# LCD-24.net
KiCad netlist of a schematic drawn in Altium Designer
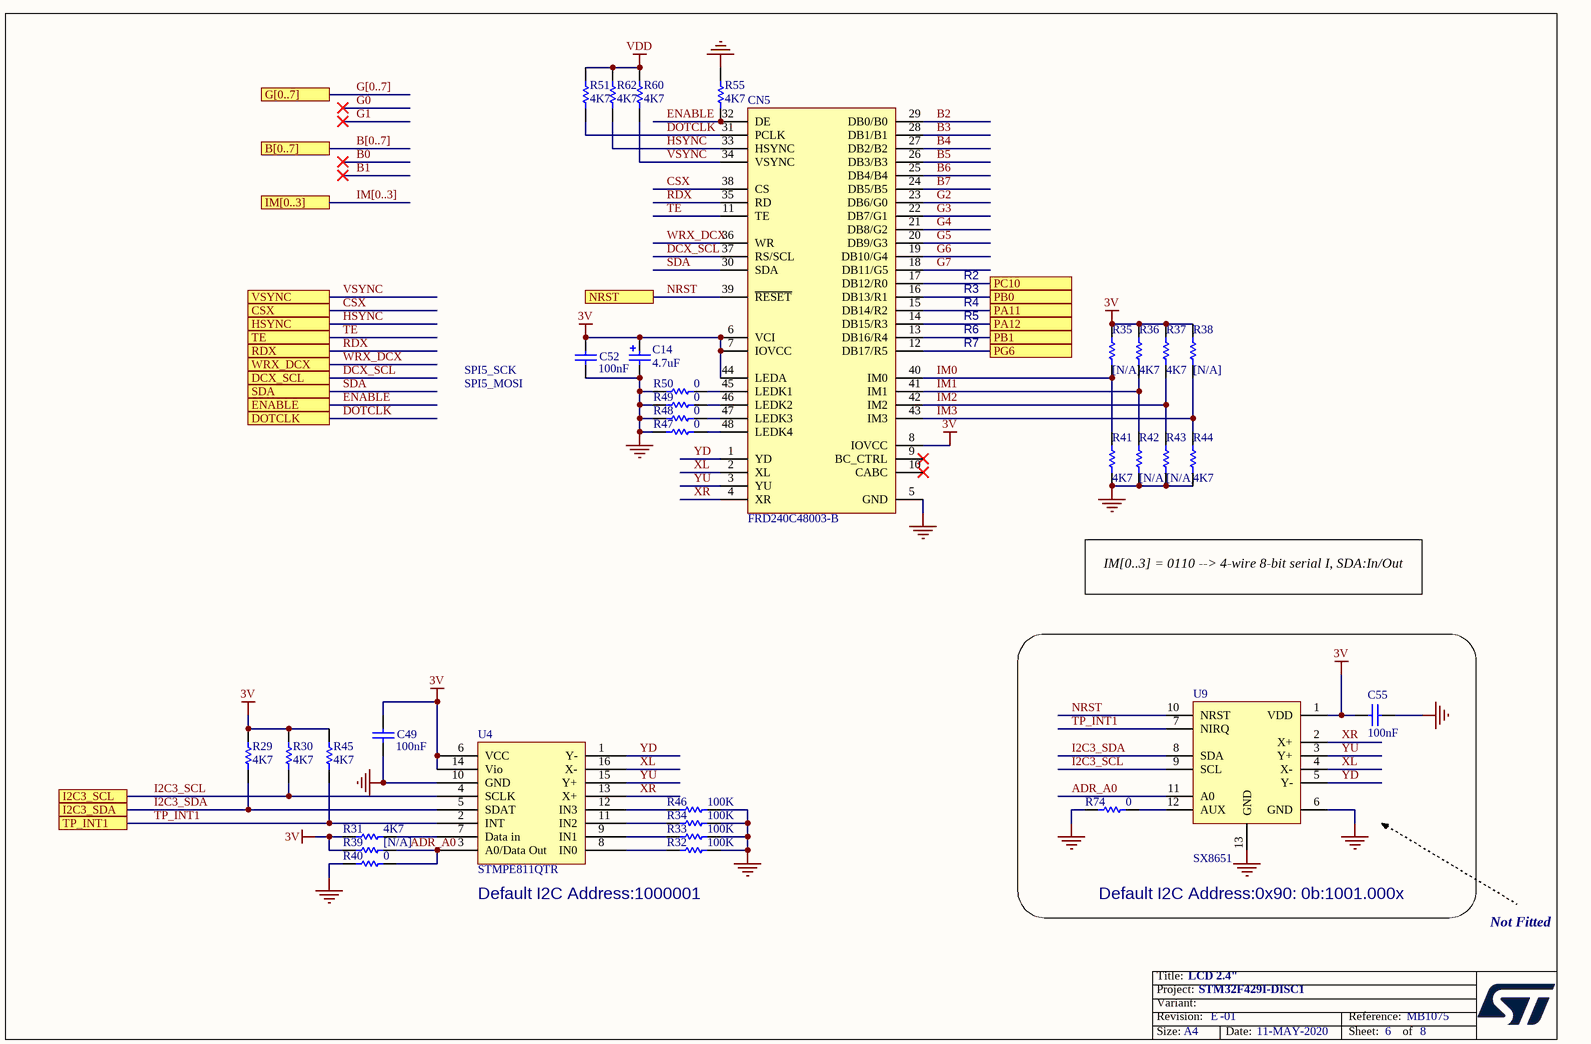
[diagram p0: LCD-24.SchDoc]

(export (version "E")
  (design (tool "Eeschema 10.0.6"))
  (components
    (comp (ref "C14")
      (value "4.7uF")
      (footprint "TAN-A")
      (description "Polarized Capacitor (Radial)")
      (fields (field (name "PUBLISHER") "Altium Limited"))
      (libsource (lib "Miscellaneous Devices") (part "Cap Pol1"))
    )
    (comp (ref "C49")
      (value "100nF")
      (footprint "0402C")
      (description "Capacitor 0402 / 0603 / 0805")
      (libsource (lib "MCD_TOOLS") (part "Capacitor_ST"))
    )
    (comp (ref "C52")
      (value "100nF")
      (footprint "0402C")
      (description "Capacitor 0402 / 0603 / 0805")
      (libsource (lib "MCD_TOOLS") (part "Capacitor_ST"))
    )
    (comp (ref "C55")
      (value "100nF")
      (footprint "0402C")
      (description "Capacitor 0402 / 0603 / 0805")
      (libsource (lib "MCD_TOOLS") (part "Capacitor_ST"))
    )
    (comp (ref "CN5")
      (value "FRD240C48003-B")
      (footprint "LCD_FRIDA_FRD240C48003-B")
      (description "TFT LCD 2.4inch 240RGB x 320 pixels + RTP")
      (fields
        (field (name "INTERNAL_PART_NUMBER") "MCD-02110")
        (field (name "MANUFACTURER") "FRIDA SHENZEN LCD CO.LTD")
      )
      (libsource (lib "MCD_PARTS_database") (part "FRD240C48003-B"))
    )
    (comp (ref "R29")
      (value "4K7")
      (footprint "0402R")
      (description "Resistor 0402 / 0603 / 0805")
      (libsource (lib "MCD_TOOLS") (part "Resistor_ST"))
    )
    (comp (ref "R30")
      (value "4K7")
      (footprint "0402R")
      (description "Resistor 0402 / 0603 / 0805")
      (libsource (lib "MCD_TOOLS") (part "Resistor_ST"))
    )
    (comp (ref "R31")
      (value "4K7")
      (footprint "0402R")
      (description "Resistor 0402 / 0603 / 0805")
      (libsource (lib "MCD_TOOLS") (part "Resistor_ST"))
    )
    (comp (ref "R32")
      (value "100K")
      (footprint "0402R")
      (description "Resistor 0402 / 0603 / 0805")
      (libsource (lib "MCD_TOOLS") (part "Resistor_ST"))
    )
    (comp (ref "R33")
      (value "100K")
      (footprint "0402R")
      (description "Resistor 0402 / 0603 / 0805")
      (libsource (lib "MCD_TOOLS") (part "Resistor_ST"))
    )
    (comp (ref "R34")
      (value "100K")
      (footprint "0402R")
      (description "Resistor 0402 / 0603 / 0805")
      (libsource (lib "MCD_TOOLS") (part "Resistor_ST"))
    )
    (comp (ref "R35")
      (value "[N/A]")
      (footprint "0402R")
      (description "Resistor 0402 / 0603 / 0805")
      (libsource (lib "MCD_TOOLS") (part "Resistor_ST"))
    )
    (comp (ref "R36")
      (value "4K7")
      (footprint "0402R")
      (description "Resistor 0402 / 0603 / 0805")
      (libsource (lib "MCD_TOOLS") (part "Resistor_ST"))
    )
    (comp (ref "R37")
      (value "4K7")
      (footprint "0402R")
      (description "Resistor 0402 / 0603 / 0805")
      (libsource (lib "MCD_TOOLS") (part "Resistor_ST"))
    )
    (comp (ref "R38")
      (value "[N/A]")
      (footprint "0402R")
      (description "Resistor 0402 / 0603 / 0805")
      (libsource (lib "MCD_TOOLS") (part "Resistor_ST"))
    )
    (comp (ref "R39")
      (value "[N/A]")
      (footprint "0402R")
      (description "Resistor 0402 / 0603 / 0805")
      (libsource (lib "MCD_TOOLS") (part "Resistor_ST"))
    )
    (comp (ref "R40")
      (value "0")
      (footprint "0402R")
      (description "Resistor 0402 / 0603 / 0805")
      (libsource (lib "MCD_TOOLS") (part "Resistor_ST"))
    )
    (comp (ref "R41")
      (value "4K7")
      (footprint "0402R")
      (description "Resistor 0402 / 0603 / 0805")
      (libsource (lib "MCD_TOOLS") (part "Resistor_ST"))
    )
    (comp (ref "R42")
      (value "[N/A]")
      (footprint "0402R")
      (description "Resistor 0402 / 0603 / 0805")
      (libsource (lib "MCD_TOOLS") (part "Resistor_ST"))
    )
    (comp (ref "R43")
      (value "[N/A]")
      (footprint "0402R")
      (description "Resistor 0402 / 0603 / 0805")
      (libsource (lib "MCD_TOOLS") (part "Resistor_ST"))
    )
    (comp (ref "R44")
      (value "4K7")
      (footprint "0402R")
      (description "Resistor 0402 / 0603 / 0805")
      (libsource (lib "MCD_TOOLS") (part "Resistor_ST"))
    )
    (comp (ref "R45")
      (value "4K7")
      (footprint "0402R")
      (description "Resistor 0402 / 0603 / 0805")
      (libsource (lib "MCD_TOOLS") (part "Resistor_ST"))
    )
    (comp (ref "R46")
      (value "100K")
      (footprint "0402R")
      (description "Resistor 0402 / 0603 / 0805")
      (libsource (lib "MCD_TOOLS") (part "Resistor_ST"))
    )
    (comp (ref "R47")
      (value "0")
      (footprint "0603R")
      (description "Resistor 0402 / 0603 / 0805")
      (libsource (lib "MCD_TOOLS") (part "Resistor_ST"))
    )
    (comp (ref "R48")
      (value "0")
      (footprint "0603R")
      (description "Resistor 0402 / 0603 / 0805")
      (libsource (lib "MCD_TOOLS") (part "Resistor_ST"))
    )
    (comp (ref "R49")
      (value "0")
      (footprint "0603R")
      (description "Resistor 0402 / 0603 / 0805")
      (libsource (lib "MCD_TOOLS") (part "Resistor_ST"))
    )
    (comp (ref "R50")
      (value "0")
      (footprint "0603R")
      (description "Resistor 0402 / 0603 / 0805")
      (libsource (lib "MCD_TOOLS") (part "Resistor_ST"))
    )
    (comp (ref "R51")
      (value "4K7")
      (footprint "0402R")
      (description "Resistor 0402 / 0603 / 0805")
      (libsource (lib "MCD_TOOLS") (part "Resistor_ST"))
    )
    (comp (ref "R55")
      (value "4K7")
      (footprint "0402R")
      (description "Resistor 0402 / 0603 / 0805")
      (libsource (lib "MCD_TOOLS") (part "Resistor_ST"))
    )
    (comp (ref "R60")
      (value "4K7")
      (footprint "0402R")
      (description "Resistor 0402 / 0603 / 0805")
      (libsource (lib "MCD_TOOLS") (part "Resistor_ST"))
    )
    (comp (ref "R62")
      (value "4K7")
      (footprint "0402R")
      (description "Resistor 0402 / 0603 / 0805")
      (libsource (lib "MCD_TOOLS") (part "Resistor_ST"))
    )
    (comp (ref "R74")
      (value "0")
      (footprint "0402R")
      (description "Resistor 0402 / 0603 / 0805")
      (libsource (lib "MCD_TOOLS") (part "Resistor_ST"))
    )
    (comp (ref "U4")
      (value "STMPE811QTR")
      (footprint "QFN16_3X3")
      (description "S-Touch® advanced resistive touchscreen controller, with 8-bit GPIO expander")
      (libsource (lib "MCD_TOOLS") (part "STMPE811"))
    )
    (comp (ref "U9")
      (value "SX8651")
      (footprint "ICC_DFN12-EPAD_3X3_P045")
      (description "Multitouch 4-wire Resistive Touchscreen Controller with 15kV ESD Protection")
      (fields
        (field (name "INTERNAL_PART_NUMBER") "MCD-01952")
        (field (name "MANUFACTURER_PART_NUMBER") "SX8651IWLTRT")
        (field (name "PROVIDED_BY") "SUBCO")
      )
      (libsource (lib "MCD_PARTS_database") (part "SX8651"))
    )
  )
  (nets
    (net (code "1") (name "/ADR_A0") (class "Default")
      (node (ref "R39") (pin "2") (pinfunction "2_2") (pintype "passive"))
      (node (ref "R40") (pin "2") (pinfunction "2_2") (pintype "passive"))
      (node (ref "U4") (pin "3") (pinfunction "A0/Data_Out_3") (pintype "passive"))
      (node (ref "U9") (pin "11") (pinfunction "A0_11") (pintype "passive"))
    )
    (net (code "4") (name "/B2") (class "Default")
      (node (ref "CN5") (pin "29") (pinfunction "DB0/B0_29") (pintype "passive"))
    )
    (net (code "5") (name "/B3") (class "Default")
      (node (ref "CN5") (pin "28") (pinfunction "DB1/B1_28") (pintype "passive"))
    )
    (net (code "6") (name "/B4") (class "Default")
      (node (ref "CN5") (pin "27") (pinfunction "DB2/B2_27") (pintype "passive"))
    )
    (net (code "7") (name "/B5") (class "Default")
      (node (ref "CN5") (pin "26") (pinfunction "DB3/B3_26") (pintype "passive"))
    )
    (net (code "8") (name "/B6") (class "Default")
      (node (ref "CN5") (pin "25") (pinfunction "DB4/B4_25") (pintype "passive"))
    )
    (net (code "9") (name "/B7") (class "Default")
      (node (ref "CN5") (pin "24") (pinfunction "DB5/B5_24") (pintype "passive"))
    )
    (net (code "11") (name "/CSX") (class "Default")
      (node (ref "CN5") (pin "38") (pinfunction "CS_38") (pintype "passive"))
    )
    (net (code "12") (name "/DCX_SCL") (class "Default")
      (node (ref "CN5") (pin "37") (pinfunction "RS/SCL_37") (pintype "passive"))
    )
    (net (code "13") (name "/DOTCLK") (class "Default")
      (node (ref "CN5") (pin "31") (pinfunction "PCLK_31") (pintype "passive"))
      (node (ref "R51") (pin "1") (pinfunction "1_1") (pintype "passive"))
    )
    (net (code "14") (name "/ENABLE") (class "Default")
      (node (ref "CN5") (pin "32") (pinfunction "DE_32") (pintype "passive"))
      (node (ref "R55") (pin "1") (pinfunction "1_1") (pintype "passive"))
    )
    (net (code "17") (name "/G2") (class "Default")
      (node (ref "CN5") (pin "23") (pinfunction "DB6/G0_23") (pintype "passive"))
    )
    (net (code "18") (name "/G3") (class "Default")
      (node (ref "CN5") (pin "22") (pinfunction "DB7/G1_22") (pintype "passive"))
    )
    (net (code "19") (name "/G4") (class "Default")
      (node (ref "CN5") (pin "21") (pinfunction "DB8/G2_21") (pintype "passive"))
    )
    (net (code "20") (name "/G5") (class "Default")
      (node (ref "CN5") (pin "20") (pinfunction "DB9/G3_20") (pintype "passive"))
    )
    (net (code "21") (name "/G6") (class "Default")
      (node (ref "CN5") (pin "19") (pinfunction "DB10/G4_19") (pintype "passive"))
    )
    (net (code "22") (name "/G7") (class "Default")
      (node (ref "CN5") (pin "18") (pinfunction "DB11/G5_18") (pintype "passive"))
    )
    (net (code "24") (name "/HSYNC") (class "Default")
      (node (ref "CN5") (pin "33") (pinfunction "HSYNC_33") (pintype "passive"))
      (node (ref "R62") (pin "1") (pinfunction "1_1") (pintype "passive"))
    )
    (net (code "25") (name "/I2C3_SCL") (class "Default")
      (node (ref "R30") (pin "1") (pinfunction "1_1") (pintype "passive"))
      (node (ref "U4") (pin "4") (pinfunction "SCLK_4") (pintype "passive"))
      (node (ref "U9") (pin "9") (pinfunction "SCL_9") (pintype "passive"))
    )
    (net (code "26") (name "/I2C3_SDA") (class "Default")
      (node (ref "R29") (pin "1") (pinfunction "1_1") (pintype "passive"))
      (node (ref "U4") (pin "5") (pinfunction "SDAT_5") (pintype "passive"))
      (node (ref "U9") (pin "8") (pinfunction "SDA_8") (pintype "passive"))
    )
    (net (code "27") (name "/IM0") (class "Default")
      (node (ref "CN5") (pin "40") (pinfunction "IM0_40") (pintype "passive"))
      (node (ref "R35") (pin "1") (pinfunction "1_1") (pintype "passive"))
      (node (ref "R41") (pin "2") (pinfunction "2_2") (pintype "passive"))
    )
    (net (code "28") (name "/IM1") (class "Default")
      (node (ref "CN5") (pin "41") (pinfunction "IM1_41") (pintype "passive"))
      (node (ref "R36") (pin "1") (pinfunction "1_1") (pintype "passive"))
      (node (ref "R42") (pin "2") (pinfunction "2_2") (pintype "passive"))
    )
    (net (code "29") (name "/IM2") (class "Default")
      (node (ref "CN5") (pin "42") (pinfunction "IM2_42") (pintype "passive"))
      (node (ref "R37") (pin "1") (pinfunction "1_1") (pintype "passive"))
      (node (ref "R43") (pin "2") (pinfunction "2_2") (pintype "passive"))
    )
    (net (code "30") (name "/IM3") (class "Default")
      (node (ref "CN5") (pin "43") (pinfunction "IM3_43") (pintype "passive"))
      (node (ref "R38") (pin "1") (pinfunction "1_1") (pintype "passive"))
      (node (ref "R44") (pin "2") (pinfunction "2_2") (pintype "passive"))
    )
    (net (code "32") (name "/NRST") (class "Default")
      (node (ref "CN5") (pin "39") (pinfunction "~{RESET}_39") (pintype "passive"))
      (node (ref "U9") (pin "10") (pinfunction "NRST_10") (pintype "passive"))
    )
    (net (code "33") (name "/PA11") (class "Default")
      (node (ref "CN5") (pin "15") (pinfunction "DB14/R2_15") (pintype "passive"))
    )
    (net (code "34") (name "/PA12") (class "Default")
      (node (ref "CN5") (pin "14") (pinfunction "DB15/R3_14") (pintype "passive"))
    )
    (net (code "35") (name "/PB0") (class "Default")
      (node (ref "CN5") (pin "16") (pinfunction "DB13/R1_16") (pintype "passive"))
    )
    (net (code "36") (name "/PB1") (class "Default")
      (node (ref "CN5") (pin "13") (pinfunction "DB16/R4_13") (pintype "passive"))
    )
    (net (code "37") (name "/PC10") (class "Default")
      (node (ref "CN5") (pin "17") (pinfunction "DB12/R0_17") (pintype "passive"))
    )
    (net (code "38") (name "/PG6") (class "Default")
      (node (ref "CN5") (pin "12") (pinfunction "DB17/R5_12") (pintype "passive"))
    )
    (net (code "39") (name "/RDX") (class "Default")
      (node (ref "CN5") (pin "35") (pinfunction "RD_35") (pintype "passive"))
    )
    (net (code "40") (name "/SDA") (class "Default")
      (node (ref "CN5") (pin "30") (pinfunction "SDA_30") (pintype "passive"))
    )
    (net (code "41") (name "/TE") (class "Default")
      (node (ref "CN5") (pin "11") (pinfunction "TE_11") (pintype "passive"))
    )
    (net (code "42") (name "/TP_INT1") (class "Default")
      (node (ref "R45") (pin "1") (pinfunction "1_1") (pintype "passive"))
      (node (ref "U4") (pin "2") (pinfunction "INT_2") (pintype "passive"))
      (node (ref "U9") (pin "7") (pinfunction "NIRQ_7") (pintype "passive"))
    )
    (net (code "43") (name "/VSYNC") (class "Default")
      (node (ref "CN5") (pin "34") (pinfunction "VSYNC_34") (pintype "passive"))
      (node (ref "R60") (pin "1") (pinfunction "1_1") (pintype "passive"))
    )
    (net (code "44") (name "/WRX_DCX") (class "Default")
      (node (ref "CN5") (pin "36") (pinfunction "WR_36") (pintype "passive"))
    )
    (net (code "45") (name "/XL") (class "Default")
      (node (ref "CN5") (pin "2") (pinfunction "XL_2") (pintype "passive"))
      (node (ref "U4") (pin "16") (pinfunction "X-_16") (pintype "passive"))
      (node (ref "U9") (pin "4") (pinfunction "X-_4") (pintype "passive"))
    )
    (net (code "46") (name "/XR") (class "Default")
      (node (ref "CN5") (pin "4") (pinfunction "XR_4") (pintype "passive"))
      (node (ref "U4") (pin "13") (pinfunction "X+_13") (pintype "passive"))
      (node (ref "U9") (pin "2") (pinfunction "X+_2") (pintype "passive"))
    )
    (net (code "47") (name "/YD") (class "Default")
      (node (ref "CN5") (pin "1") (pinfunction "YD_1") (pintype "passive"))
      (node (ref "U4") (pin "1") (pinfunction "Y-_1") (pintype "passive"))
      (node (ref "U9") (pin "5") (pinfunction "Y-_5") (pintype "passive"))
    )
    (net (code "48") (name "/YU") (class "Default")
      (node (ref "CN5") (pin "3") (pinfunction "YU_3") (pintype "passive"))
      (node (ref "U4") (pin "15") (pinfunction "Y+_15") (pintype "passive"))
      (node (ref "U9") (pin "3") (pinfunction "Y+_3") (pintype "passive"))
    )
    (net (code "49") (name "3V") (class "Default")
      (node (ref "C14") (pin "1") (pinfunction "1_1") (pintype "passive"))
      (node (ref "C49") (pin "2") (pinfunction "2_2") (pintype "passive"))
      (node (ref "C52") (pin "2") (pinfunction "2_2") (pintype "passive"))
      (node (ref "C55") (pin "1") (pinfunction "1_1") (pintype "passive"))
      (node (ref "CN5") (pin "44") (pinfunction "LEDA_44") (pintype "passive"))
      (node (ref "CN5") (pin "6") (pinfunction "VCI_6") (pintype "passive"))
      (node (ref "CN5") (pin "7") (pinfunction "IOVCC_7") (pintype "passive"))
      (node (ref "CN5") (pin "8") (pinfunction "IOVCC_8") (pintype "passive"))
      (node (ref "R29") (pin "2") (pinfunction "2_2") (pintype "passive"))
      (node (ref "R30") (pin "2") (pinfunction "2_2") (pintype "passive"))
      (node (ref "R31") (pin "1") (pinfunction "1_1") (pintype "passive"))
      (node (ref "R35") (pin "2") (pinfunction "2_2") (pintype "passive"))
      (node (ref "R36") (pin "2") (pinfunction "2_2") (pintype "passive"))
      (node (ref "R37") (pin "2") (pinfunction "2_2") (pintype "passive"))
      (node (ref "R38") (pin "2") (pinfunction "2_2") (pintype "passive"))
      (node (ref "R39") (pin "1") (pinfunction "1_1") (pintype "passive"))
      (node (ref "R45") (pin "2") (pinfunction "2_2") (pintype "passive"))
      (node (ref "U4") (pin "14") (pinfunction "Vio_14") (pintype "passive"))
      (node (ref "U4") (pin "6") (pinfunction "VCC_6") (pintype "passive"))
      (node (ref "U9") (pin "1") (pinfunction "VDD_1") (pintype "passive"))
    )
    (net (code "50") (name "GND") (class "Default")
      (node (ref "C14") (pin "2") (pinfunction "2_2") (pintype "passive"))
      (node (ref "C49") (pin "1") (pinfunction "1_1") (pintype "passive"))
      (node (ref "C52") (pin "1") (pinfunction "1_1") (pintype "passive"))
      (node (ref "C55") (pin "2") (pinfunction "2_2") (pintype "passive"))
      (node (ref "CN5") (pin "5") (pinfunction "GND_5") (pintype "passive"))
      (node (ref "R32") (pin "2") (pinfunction "2_2") (pintype "passive"))
      (node (ref "R33") (pin "2") (pinfunction "2_2") (pintype "passive"))
      (node (ref "R34") (pin "2") (pinfunction "2_2") (pintype "passive"))
      (node (ref "R40") (pin "1") (pinfunction "1_1") (pintype "passive"))
      (node (ref "R41") (pin "1") (pinfunction "1_1") (pintype "passive"))
      (node (ref "R42") (pin "1") (pinfunction "1_1") (pintype "passive"))
      (node (ref "R43") (pin "1") (pinfunction "1_1") (pintype "passive"))
      (node (ref "R44") (pin "1") (pinfunction "1_1") (pintype "passive"))
      (node (ref "R46") (pin "2") (pinfunction "2_2") (pintype "passive"))
      (node (ref "R47") (pin "1") (pinfunction "1_1") (pintype "passive"))
      (node (ref "R48") (pin "1") (pinfunction "1_1") (pintype "passive"))
      (node (ref "R49") (pin "1") (pinfunction "1_1") (pintype "passive"))
      (node (ref "R50") (pin "1") (pinfunction "1_1") (pintype "passive"))
      (node (ref "R55") (pin "2") (pinfunction "2_2") (pintype "passive"))
      (node (ref "R74") (pin "1") (pinfunction "1_1") (pintype "passive"))
      (node (ref "U4") (pin "10") (pinfunction "GND_10") (pintype "passive"))
      (node (ref "U9") (pin "13") (pinfunction "GND_13") (pintype "passive"))
      (node (ref "U9") (pin "6") (pinfunction "GND_6") (pintype "passive"))
    )
    (net (code "51") (name "Net-(CN5-LEDK1)") (class "Default")
      (node (ref "CN5") (pin "45") (pinfunction "LEDK1_45") (pintype "passive"))
      (node (ref "R50") (pin "2") (pinfunction "2_2") (pintype "passive"))
    )
    (net (code "52") (name "Net-(CN5-LEDK2)") (class "Default")
      (node (ref "CN5") (pin "46") (pinfunction "LEDK2_46") (pintype "passive"))
      (node (ref "R49") (pin "2") (pinfunction "2_2") (pintype "passive"))
    )
    (net (code "53") (name "Net-(CN5-LEDK3)") (class "Default")
      (node (ref "CN5") (pin "47") (pinfunction "LEDK3_47") (pintype "passive"))
      (node (ref "R48") (pin "2") (pinfunction "2_2") (pintype "passive"))
    )
    (net (code "54") (name "Net-(CN5-LEDK4)") (class "Default")
      (node (ref "CN5") (pin "48") (pinfunction "LEDK4_48") (pintype "passive"))
      (node (ref "R47") (pin "2") (pinfunction "2_2") (pintype "passive"))
    )
    (net (code "55") (name "Net-(U4-Data_in)") (class "Default")
      (node (ref "R31") (pin "2") (pinfunction "2_2") (pintype "passive"))
      (node (ref "U4") (pin "7") (pinfunction "Data_in_7") (pintype "passive"))
    )
    (net (code "56") (name "Net-(U4-IN0)") (class "Default")
      (node (ref "R32") (pin "1") (pinfunction "1_1") (pintype "passive"))
      (node (ref "U4") (pin "8") (pinfunction "IN0_8") (pintype "passive"))
    )
    (net (code "57") (name "Net-(U4-IN1)") (class "Default")
      (node (ref "R33") (pin "1") (pinfunction "1_1") (pintype "passive"))
      (node (ref "U4") (pin "9") (pinfunction "IN1_9") (pintype "passive"))
    )
    (net (code "58") (name "Net-(U4-IN2)") (class "Default")
      (node (ref "R34") (pin "1") (pinfunction "1_1") (pintype "passive"))
      (node (ref "U4") (pin "11") (pinfunction "IN2_11") (pintype "passive"))
    )
    (net (code "59") (name "Net-(U4-IN3)") (class "Default")
      (node (ref "R46") (pin "1") (pinfunction "1_1") (pintype "passive"))
      (node (ref "U4") (pin "12") (pinfunction "IN3_12") (pintype "passive"))
    )
    (net (code "60") (name "Net-(U9-AUX)") (class "Default")
      (node (ref "R74") (pin "2") (pinfunction "2_2") (pintype "passive"))
      (node (ref "U9") (pin "12") (pinfunction "AUX_12") (pintype "passive"))
    )
    (net (code "61") (name "VDD") (class "Default")
      (node (ref "R51") (pin "2") (pinfunction "2_2") (pintype "passive"))
      (node (ref "R60") (pin "2") (pinfunction "2_2") (pintype "passive"))
      (node (ref "R62") (pin "2") (pinfunction "2_2") (pintype "passive"))
    )
    (net (code "62") (name "unconnected-(CN5-BC_CTRL-Pad9)") (class "Default")
      (node (ref "CN5") (pin "9") (pinfunction "BC_CTRL_9") (pintype "passive+no_connect"))
    )
    (net (code "63") (name "unconnected-(CN5-CABC-Pad10)") (class "Default")
      (node (ref "CN5") (pin "10") (pinfunction "CABC_10") (pintype "passive+no_connect"))
    )
  )
)
